# Bluetooth.net
KiCad netlist of a schematic drawn in Altium Designer
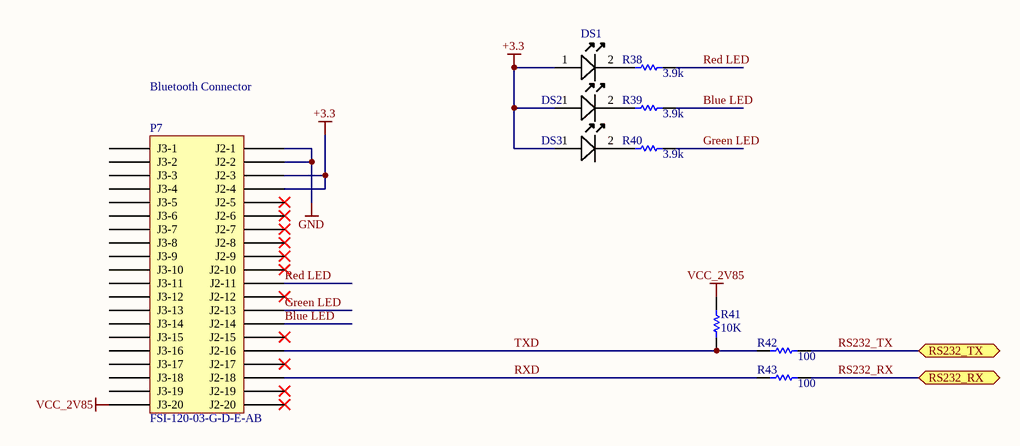
[diagram p0: Bluetooth.SchDoc]

(export (version "E")
  (design (tool "Eeschema 10.0.6"))
  (components
    (comp (ref "DS1")
      (value "Lite-On LTST-S220KGKT Green LED, 571 nm 2012 (0805) Side View, Rectangle Lens SMD package")
      (footprint "0805C_L")
      (fields
        (field (name "MANUFACTURER") "Vishay / Lite-On")
        (field (name "MANUFACTURER PART NUMBER") "LTST-S220KGKT")
      )
      (libsource (lib "*") (part "LED A/K"))
    )
    (comp (ref "DS2")
      (value "Lite-On LTST-S220KGKT Green LED, 571 nm 2012 (0805) Side View, Rectangle Lens SMD package")
      (footprint "0805C_L")
      (fields
        (field (name "MANUFACTURER") "Vishay / Lite-On")
        (field (name "MANUFACTURER PART NUMBER") "LTST-S220KGKT")
      )
      (libsource (lib "*") (part "LED A/K"))
    )
    (comp (ref "DS3")
      (value "Lite-On LTST-S220KGKT Green LED, 571 nm 2012 (0805) Side View, Rectangle Lens SMD package")
      (footprint "0805C_L")
      (fields
        (field (name "MANUFACTURER") "Vishay / Lite-On")
        (field (name "MANUFACTURER PART NUMBER") "LTST-S220KGKT")
      )
      (libsource (lib "*") (part "LED A/K"))
    )
    (comp (ref "P7")
      (value "FSI-120-03-G-D-E-AB")
      (footprint "FSI-120-03-G-D-E-AB")
      (fields (field (name "SUPPLIER PART NUMBER 1") "FSI-120-03-G-D-E-AB"))
      (libsource (lib "ZLS_Schematic_lib") (part "FSI-120-03-G-D-E-AB"))
    )
    (comp (ref "R38")
      (value "3.9k")
      (footprint "RESC0805(2012)_L")
      (description "2R55 0.125W 1% 0805 (2012 Metric)  SMD")
      (fields (field (name "TOLERANCE") "1 %") (field (name "POWER") "0.125 W"))
      (libsource (lib "Altium Content Vault") (part "CMP-1013-00215-1"))
    )
    (comp (ref "R39")
      (value "3.9k")
      (footprint "RESC0805(2012)_L")
      (description "2R55 0.125W 1% 0805 (2012 Metric)  SMD")
      (fields (field (name "TOLERANCE") "1 %") (field (name "POWER") "0.125 W"))
      (libsource (lib "Altium Content Vault") (part "CMP-1013-00215-1"))
    )
    (comp (ref "R40")
      (value "3.9k")
      (footprint "RESC0805(2012)_L")
      (description "2R55 0.125W 1% 0805 (2012 Metric)  SMD")
      (fields (field (name "TOLERANCE") "1 %") (field (name "POWER") "0.125 W"))
      (libsource (lib "Altium Content Vault") (part "CMP-1013-00215-1"))
    )
    (comp (ref "R41")
      (value "10K")
      (footprint "RESC0805(2012)_L")
      (description "2R55 0.125W 1% 0805 (2012 Metric)  SMD")
      (fields (field (name "TOLERANCE") "1 %") (field (name "POWER") "0.125 W"))
      (libsource (lib "Altium Content Vault") (part "CMP-1013-00215-1"))
    )
    (comp (ref "R42")
      (value "100")
      (footprint "RESC0805(2012)_L")
      (description "2R55 0.125W 1% 0805 (2012 Metric)  SMD")
      (fields (field (name "TOLERANCE") "1 %") (field (name "POWER") "0.125 W"))
      (libsource (lib "Altium Content Vault") (part "CMP-1013-00215-1"))
    )
    (comp (ref "R43")
      (value "100")
      (footprint "RESC0805(2012)_L")
      (description "2R55 0.125W 1% 0805 (2012 Metric)  SMD")
      (fields (field (name "TOLERANCE") "1 %") (field (name "POWER") "0.125 W"))
      (libsource (lib "Altium Content Vault") (part "CMP-1013-00215-1"))
    )
  )
  (nets
    (net (code "1") (name "+3.3") (class "Default")
      (node (ref "DS1") (pin "1") (pinfunction "A_1") (pintype "passive"))
      (node (ref "DS2") (pin "1") (pinfunction "A_1") (pintype "passive"))
      (node (ref "DS3") (pin "1") (pinfunction "A_1") (pintype "passive"))
      (node (ref "P7") (pin "J2-3") (pinfunction "J2-3_J2-3") (pintype "passive"))
      (node (ref "P7") (pin "J2-4") (pinfunction "J2-4_J2-4") (pintype "passive"))
    )
    (net (code "2") (name "/Blue LED") (class "Default")
      (node (ref "P7") (pin "J2-14") (pinfunction "J2-14_J2-14") (pintype "passive"))
      (node (ref "R39") (pin "1") (pinfunction "1_1") (pintype "passive"))
    )
    (net (code "3") (name "/Green LED") (class "Default")
      (node (ref "P7") (pin "J2-13") (pinfunction "J2-13_J2-13") (pintype "passive"))
      (node (ref "R40") (pin "1") (pinfunction "1_1") (pintype "passive"))
    )
    (net (code "4") (name "/RS232_RX") (class "Default")
      (node (ref "R43") (pin "1") (pinfunction "1_1") (pintype "passive"))
    )
    (net (code "5") (name "/RS232_TX") (class "Default")
      (node (ref "R42") (pin "1") (pinfunction "1_1") (pintype "passive"))
    )
    (net (code "6") (name "/RXD") (class "Default")
      (node (ref "P7") (pin "J2-18") (pinfunction "J2-18_J2-18") (pintype "passive"))
      (node (ref "R43") (pin "2") (pinfunction "2_2") (pintype "passive"))
    )
    (net (code "7") (name "/Red LED") (class "Default")
      (node (ref "P7") (pin "J2-11") (pinfunction "J2-11_J2-11") (pintype "passive"))
      (node (ref "R38") (pin "1") (pinfunction "1_1") (pintype "passive"))
    )
    (net (code "8") (name "/TXD") (class "Default")
      (node (ref "P7") (pin "J2-16") (pinfunction "J2-16_J2-16") (pintype "passive"))
      (node (ref "R41") (pin "2") (pinfunction "2_2") (pintype "passive"))
      (node (ref "R42") (pin "2") (pinfunction "2_2") (pintype "passive"))
    )
    (net (code "9") (name "GND") (class "Default")
      (node (ref "P7") (pin "J2-1") (pinfunction "J2-1_J2-1") (pintype "passive"))
      (node (ref "P7") (pin "J2-2") (pinfunction "J2-2_J2-2") (pintype "passive"))
    )
    (net (code "10") (name "Net-(DS1-K)") (class "Default")
      (node (ref "DS1") (pin "2") (pinfunction "K_2") (pintype "passive"))
      (node (ref "R38") (pin "2") (pinfunction "2_2") (pintype "passive"))
    )
    (net (code "11") (name "Net-(DS2-K)") (class "Default")
      (node (ref "DS2") (pin "2") (pinfunction "K_2") (pintype "passive"))
      (node (ref "R39") (pin "2") (pinfunction "2_2") (pintype "passive"))
    )
    (net (code "12") (name "Net-(DS3-K)") (class "Default")
      (node (ref "DS3") (pin "2") (pinfunction "K_2") (pintype "passive"))
      (node (ref "R40") (pin "2") (pinfunction "2_2") (pintype "passive"))
    )
    (net (code "13") (name "VCC_2V85") (class "Default")
      (node (ref "P7") (pin "J3-20") (pinfunction "J3-20_J3-20") (pintype "passive"))
      (node (ref "R41") (pin "1") (pinfunction "1_1") (pintype "passive"))
    )
    (net (code "14") (name "unconnected-(P7-PadJ2-5)") (class "Default")
      (node (ref "P7") (pin "J2-5") (pinfunction "J2-5_J2-5") (pintype "passive+no_connect"))
    )
    (net (code "15") (name "unconnected-(P7-PadJ2-6)") (class "Default")
      (node (ref "P7") (pin "J2-6") (pinfunction "J2-6_J2-6") (pintype "passive+no_connect"))
    )
    (net (code "16") (name "unconnected-(P7-PadJ2-7)") (class "Default")
      (node (ref "P7") (pin "J2-7") (pinfunction "J2-7_J2-7") (pintype "passive+no_connect"))
    )
    (net (code "17") (name "unconnected-(P7-PadJ2-8)") (class "Default")
      (node (ref "P7") (pin "J2-8") (pinfunction "J2-8_J2-8") (pintype "passive+no_connect"))
    )
    (net (code "18") (name "unconnected-(P7-PadJ2-9)") (class "Default")
      (node (ref "P7") (pin "J2-9") (pinfunction "J2-9_J2-9") (pintype "passive+no_connect"))
    )
    (net (code "19") (name "unconnected-(P7-PadJ2-10)") (class "Default")
      (node (ref "P7") (pin "J2-10") (pinfunction "J2-10_J2-10") (pintype "passive+no_connect"))
    )
    (net (code "20") (name "unconnected-(P7-PadJ2-12)") (class "Default")
      (node (ref "P7") (pin "J2-12") (pinfunction "J2-12_J2-12") (pintype "passive+no_connect"))
    )
    (net (code "21") (name "unconnected-(P7-PadJ2-15)") (class "Default")
      (node (ref "P7") (pin "J2-15") (pinfunction "J2-15_J2-15") (pintype "passive+no_connect"))
    )
    (net (code "22") (name "unconnected-(P7-PadJ2-17)") (class "Default")
      (node (ref "P7") (pin "J2-17") (pinfunction "J2-17_J2-17") (pintype "passive+no_connect"))
    )
    (net (code "23") (name "unconnected-(P7-PadJ2-19)") (class "Default")
      (node (ref "P7") (pin "J2-19") (pinfunction "J2-19_J2-19") (pintype "passive+no_connect"))
    )
    (net (code "24") (name "unconnected-(P7-PadJ2-20)") (class "Default")
      (node (ref "P7") (pin "J2-20") (pinfunction "J2-20_J2-20") (pintype "passive+no_connect"))
    )
    (net (code "25") (name "unconnected-(P7-PadJ3-1)") (class "Default")
      (node (ref "P7") (pin "J3-1") (pinfunction "J3-1_J3-1") (pintype "passive"))
    )
    (net (code "26") (name "unconnected-(P7-PadJ3-2)") (class "Default")
      (node (ref "P7") (pin "J3-2") (pinfunction "J3-2_J3-2") (pintype "passive"))
    )
    (net (code "27") (name "unconnected-(P7-PadJ3-3)") (class "Default")
      (node (ref "P7") (pin "J3-3") (pinfunction "J3-3_J3-3") (pintype "passive"))
    )
    (net (code "28") (name "unconnected-(P7-PadJ3-4)") (class "Default")
      (node (ref "P7") (pin "J3-4") (pinfunction "J3-4_J3-4") (pintype "passive"))
    )
    (net (code "29") (name "unconnected-(P7-PadJ3-5)") (class "Default")
      (node (ref "P7") (pin "J3-5") (pinfunction "J3-5_J3-5") (pintype "passive"))
    )
    (net (code "30") (name "unconnected-(P7-PadJ3-6)") (class "Default")
      (node (ref "P7") (pin "J3-6") (pinfunction "J3-6_J3-6") (pintype "passive"))
    )
    (net (code "31") (name "unconnected-(P7-PadJ3-7)") (class "Default")
      (node (ref "P7") (pin "J3-7") (pinfunction "J3-7_J3-7") (pintype "passive"))
    )
    (net (code "32") (name "unconnected-(P7-PadJ3-8)") (class "Default")
      (node (ref "P7") (pin "J3-8") (pinfunction "J3-8_J3-8") (pintype "passive"))
    )
    (net (code "33") (name "unconnected-(P7-PadJ3-9)") (class "Default")
      (node (ref "P7") (pin "J3-9") (pinfunction "J3-9_J3-9") (pintype "passive"))
    )
    (net (code "34") (name "unconnected-(P7-PadJ3-10)") (class "Default")
      (node (ref "P7") (pin "J3-10") (pinfunction "J3-10_J3-10") (pintype "passive"))
    )
    (net (code "35") (name "unconnected-(P7-PadJ3-11)") (class "Default")
      (node (ref "P7") (pin "J3-11") (pinfunction "J3-11_J3-11") (pintype "passive"))
    )
    (net (code "36") (name "unconnected-(P7-PadJ3-12)") (class "Default")
      (node (ref "P7") (pin "J3-12") (pinfunction "J3-12_J3-12") (pintype "passive"))
    )
    (net (code "37") (name "unconnected-(P7-PadJ3-13)") (class "Default")
      (node (ref "P7") (pin "J3-13") (pinfunction "J3-13_J3-13") (pintype "passive"))
    )
    (net (code "38") (name "unconnected-(P7-PadJ3-14)") (class "Default")
      (node (ref "P7") (pin "J3-14") (pinfunction "J3-14_J3-14") (pintype "passive"))
    )
    (net (code "39") (name "unconnected-(P7-PadJ3-15)") (class "Default")
      (node (ref "P7") (pin "J3-15") (pinfunction "J3-15_J3-15") (pintype "passive"))
    )
    (net (code "40") (name "unconnected-(P7-PadJ3-16)") (class "Default")
      (node (ref "P7") (pin "J3-16") (pinfunction "J3-16_J3-16") (pintype "passive"))
    )
    (net (code "41") (name "unconnected-(P7-PadJ3-17)") (class "Default")
      (node (ref "P7") (pin "J3-17") (pinfunction "J3-17_J3-17") (pintype "passive"))
    )
    (net (code "42") (name "unconnected-(P7-PadJ3-18)") (class "Default")
      (node (ref "P7") (pin "J3-18") (pinfunction "J3-18_J3-18") (pintype "passive"))
    )
    (net (code "43") (name "unconnected-(P7-PadJ3-19)") (class "Default")
      (node (ref "P7") (pin "J3-19") (pinfunction "J3-19_J3-19") (pintype "passive"))
    )
  )
)
